# PIR_LED_ctrl.net
KiCad netlist of a schematic drawn in EAGLE
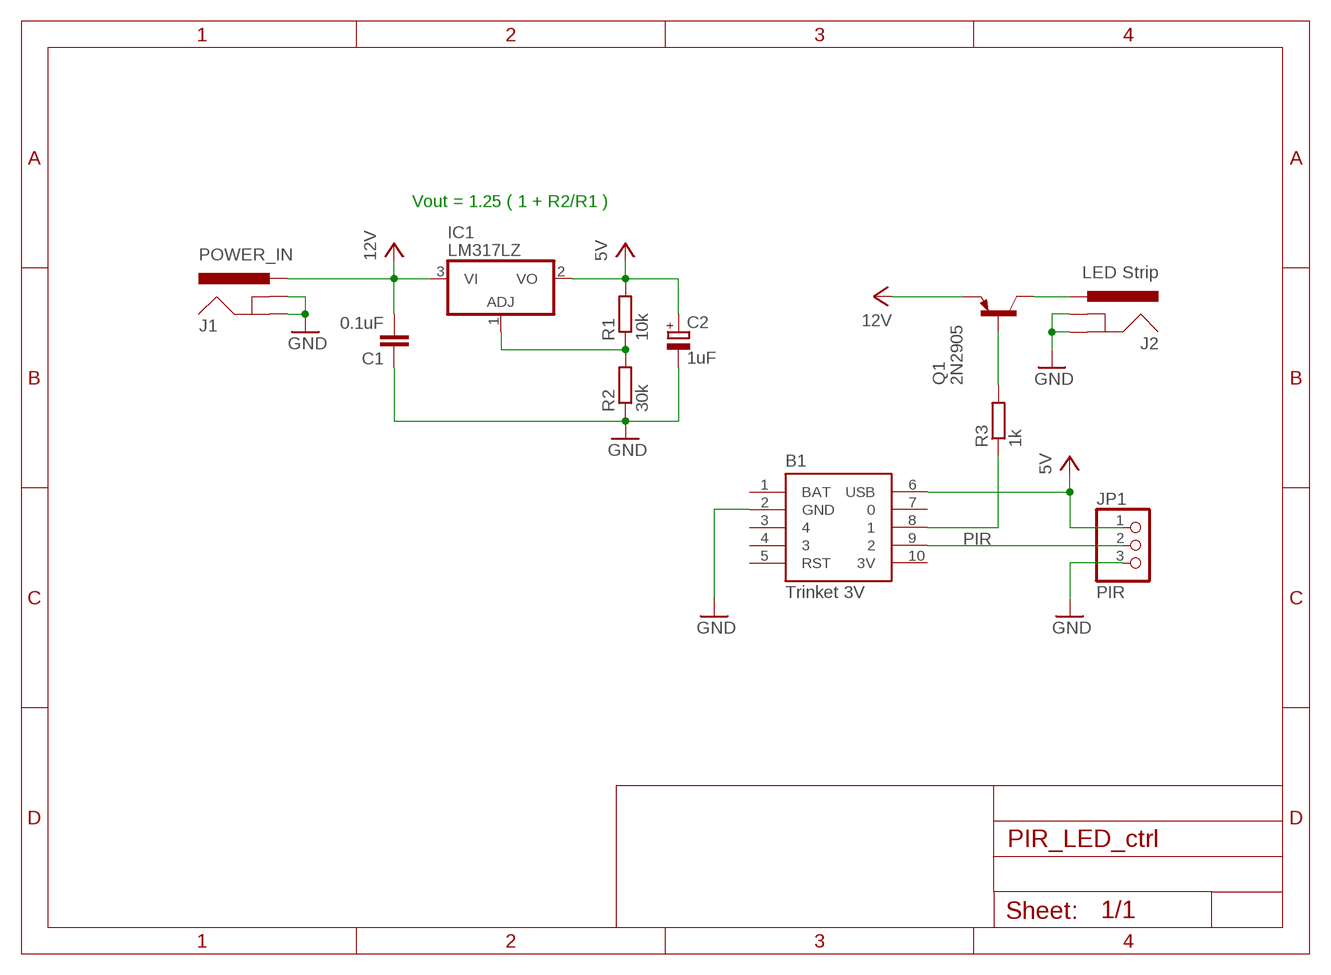
[diagram p0: schematic, sheet 1]

(export (version "E")
  (design (tool "Eeschema 10.0.6"))
  (components
    (comp (ref "B1")
      (value "Trinket 3V")
      (footprint "eagle-import:TRINKET_3V")
      (libsource (lib "eagle-import") (part "TRINKET_3V"))
    )
    (comp (ref "C1")
      (value "0.1uF")
      (footprint "eagle-import:C025-025X050")
      (libsource (lib "eagle-import") (part "C-EU025-025X050"))
    )
    (comp (ref "C2")
      (value "1uF")
      (footprint "eagle-import:E5-6")
      (libsource (lib "eagle-import") (part "CPOL-EUE5-6"))
    )
    (comp (ref "IC1")
      (value "LM317LZ")
      (footprint "eagle-import:TO92")
      (libsource (lib "eagle-import") (part "317LZLM"))
    )
    (comp (ref "J1")
      (value "POWER_IN")
      (footprint "eagle-import:POWER_JACK_PTH")
      (libsource (lib "eagle-import") (part "POWER_JACKPTH"))
    )
    (comp (ref "J2")
      (value "LED Strip")
      (footprint "eagle-import:POWER_JACK_PTH")
      (libsource (lib "eagle-import") (part "POWER_JACKPTH"))
    )
    (comp (ref "JP1")
      (value "PIR")
      (footprint "eagle-import:1X03_ROUND")
      (libsource (lib "eagle-import") (part "HEADER-1X3ROUND"))
    )
    (comp (ref "Q1")
      (value "2N2905")
      (footprint "eagle-import:TO39")
      (libsource (lib "eagle-import") (part "-PNP-TO39-EBC2N2905"))
    )
    (comp (ref "R1")
      (value "10k")
      (footprint "eagle-import:0207_10")
      (libsource (lib "eagle-import") (part "R-EU_0207/10"))
    )
    (comp (ref "R2")
      (value "30k")
      (footprint "eagle-import:0207_10")
      (libsource (lib "eagle-import") (part "R-EU_0207/10"))
    )
    (comp (ref "R3")
      (value "1k")
      (footprint "eagle-import:0207_10")
      (libsource (lib "eagle-import") (part "R-EU_0207/10"))
    )
  )
  (nets
    (net (code "1") (name "/PIR") (class "Default")
      (node (ref "B1") (pin "9") (pinfunction "2_9") (pintype "bidirectional"))
      (node (ref "JP1") (pin "2") (pinfunction "2_2") (pintype "passive"))
    )
    (net (code "2") (name "5V") (class "Default")
      (node (ref "B1") (pin "6") (pinfunction "USB_6") (pintype "bidirectional"))
      (node (ref "C2") (pin "+") (pinfunction "+_+") (pintype "passive"))
      (node (ref "IC1") (pin "2") (pinfunction "VO_2") (pintype "passive"))
      (node (ref "JP1") (pin "1") (pinfunction "1_1") (pintype "passive"))
      (node (ref "R1") (pin "2") (pinfunction "2_2") (pintype "passive"))
    )
    (net (code "3") (name "12V") (class "Default")
      (node (ref "C1") (pin "2") (pinfunction "2_2") (pintype "passive"))
      (node (ref "IC1") (pin "3") (pinfunction "VI_3") (pintype "input"))
      (node (ref "J1") (pin "PWR") (pinfunction "PWR_PWR") (pintype "bidirectional"))
      (node (ref "Q1") (pin "1") (pinfunction "E_1") (pintype "passive"))
    )
    (net (code "4") (name "GND") (class "Default")
      (node (ref "B1") (pin "2") (pinfunction "GND_2") (pintype "bidirectional"))
      (node (ref "C1") (pin "1") (pinfunction "1_1") (pintype "passive"))
      (node (ref "C2") (pin "-") (pinfunction "-_-") (pintype "passive"))
      (node (ref "J1") (pin "GND") (pinfunction "GND_GND") (pintype "bidirectional"))
      (node (ref "J1") (pin "GNDBREAK") (pinfunction "GNDBREAK_GNDBREAK") (pintype "bidirectional"))
      (node (ref "J2") (pin "GND") (pinfunction "GND_GND") (pintype "bidirectional"))
      (node (ref "J2") (pin "GNDBREAK") (pinfunction "GNDBREAK_GNDBREAK") (pintype "bidirectional"))
      (node (ref "JP1") (pin "3") (pinfunction "3_3") (pintype "passive"))
      (node (ref "R2") (pin "1") (pinfunction "1_1") (pintype "passive"))
    )
    (net (code "5") (name "Net-(B1-1)") (class "Default")
      (node (ref "B1") (pin "8") (pinfunction "1_8") (pintype "bidirectional"))
      (node (ref "R3") (pin "1") (pinfunction "1_1") (pintype "passive"))
    )
    (net (code "6") (name "Net-(IC1-ADJ)") (class "Default")
      (node (ref "IC1") (pin "1") (pinfunction "ADJ_1") (pintype "input"))
      (node (ref "R1") (pin "1") (pinfunction "1_1") (pintype "passive"))
      (node (ref "R2") (pin "2") (pinfunction "2_2") (pintype "passive"))
    )
    (net (code "7") (name "Net-(Q1-B)") (class "Default")
      (node (ref "Q1") (pin "2") (pinfunction "B_2") (pintype "passive"))
      (node (ref "R3") (pin "2") (pinfunction "2_2") (pintype "passive"))
    )
    (net (code "8") (name "Net-(Q1-C)") (class "Default")
      (node (ref "J2") (pin "PWR") (pinfunction "PWR_PWR") (pintype "bidirectional"))
      (node (ref "Q1") (pin "3") (pinfunction "C_3") (pintype "passive"))
    )
    (net (code "9") (name "unconnected-(B1-0-Pad7)") (class "Default")
      (node (ref "B1") (pin "7") (pinfunction "0_7") (pintype "bidirectional"))
    )
    (net (code "10") (name "unconnected-(B1-3-Pad4)") (class "Default")
      (node (ref "B1") (pin "4") (pinfunction "3_4") (pintype "bidirectional"))
    )
    (net (code "11") (name "unconnected-(B1-3V-Pad10)") (class "Default")
      (node (ref "B1") (pin "10") (pinfunction "3V_10") (pintype "bidirectional"))
    )
    (net (code "12") (name "unconnected-(B1-4-Pad3)") (class "Default")
      (node (ref "B1") (pin "3") (pinfunction "4_3") (pintype "bidirectional"))
    )
    (net (code "13") (name "unconnected-(B1-BAT-Pad1)") (class "Default")
      (node (ref "B1") (pin "1") (pinfunction "BAT_1") (pintype "bidirectional"))
    )
    (net (code "14") (name "unconnected-(B1-RST-Pad5)") (class "Default")
      (node (ref "B1") (pin "5") (pinfunction "RST_5") (pintype "bidirectional"))
    )
  )
)
